# 12V_Distribution_PCB.net
KiCad netlist of a schematic drawn in EasyEDA Pro
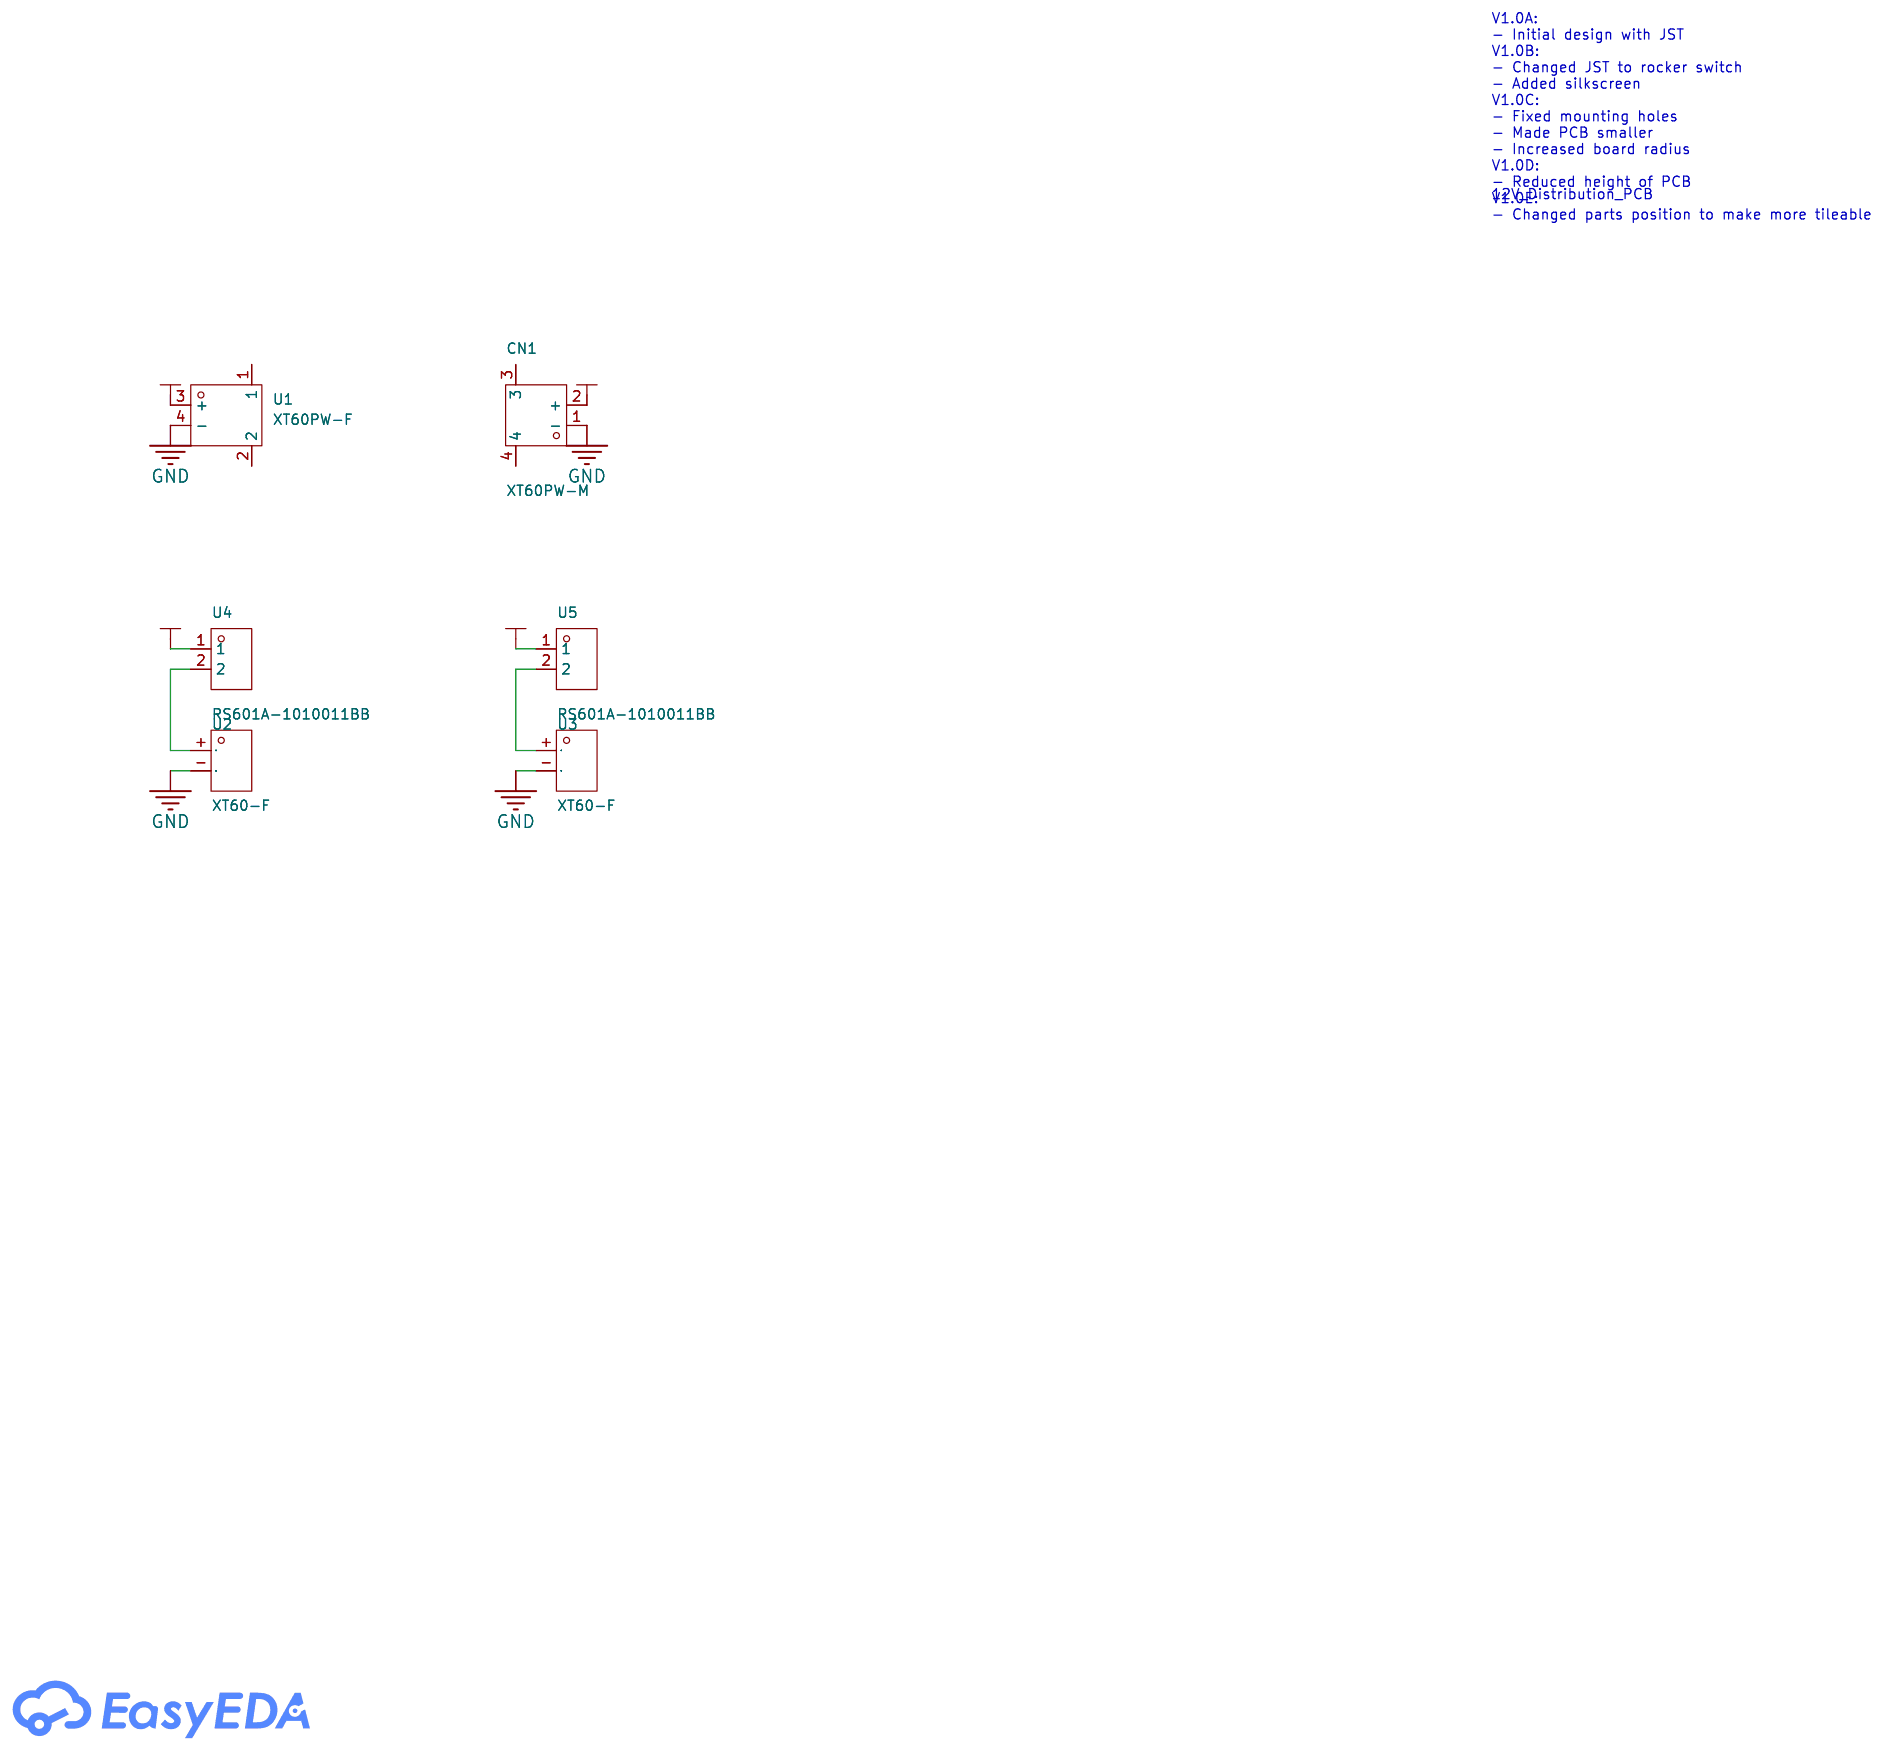
[diagram p0: schematic sheet]

(export (version "E")
  (design (tool "Eeschema 10.0.6"))
  (components
    (comp (ref "CN1")
      (value "XT60PW-M")
      (footprint "easyedapro:CONN-TH_XT60PW-M")
      (fields (field (name "Manufacturer") "AMASS(艾迈斯)"))
      (libsource (lib "easyedapro") (part "XT60PW-M"))
    )
    (comp (ref "U1")
      (value "XT60PW-F")
      (footprint "easyedapro:TH_2P-XT60PW-F")
      (fields (field (name "Manufacturer") "AMASS(艾迈斯)"))
      (libsource (lib "easyedapro") (part "XT60PW-F_C428722"))
    )
    (comp (ref "U2")
      (value "XT60-F")
      (footprint "easyedapro:CONN-TH_XT60PB-F")
      (fields (field (name "Manufacturer") "AMASS(艾迈斯)"))
      (libsource (lib "easyedapro") (part "XT60-F"))
    )
    (comp (ref "U3")
      (value "XT60-F")
      (footprint "easyedapro:CONN-TH_XT60PB-F")
      (fields (field (name "Manufacturer") "AMASS(艾迈斯)"))
      (libsource (lib "easyedapro") (part "XT60-F"))
    )
    (comp (ref "U4")
      (value "RS601A-1010011BB")
      (footprint "easyedapro:SW-TH_RS601A-1010011BB")
      (fields (field (name "Manufacturer") "HCTL(华灿天禄)"))
      (libsource (lib "easyedapro") (part "RS601A-1010011BB_C2885779"))
    )
    (comp (ref "U5")
      (value "RS601A-1010011BB")
      (footprint "easyedapro:SW-TH_RS601A-1010011BB")
      (fields (field (name "Manufacturer") "HCTL(华灿天禄)"))
      (libsource (lib "easyedapro") (part "RS601A-1010011BB_C2885779"))
    )
  )
  (nets
    (net (code "1") (name "+12V") (class "Default")
      (node (ref "CN1") (pin "2") (pinfunction "+_2") (pintype "unspecified"))
      (node (ref "U1") (pin "3") (pinfunction "+_3") (pintype "unspecified"))
      (node (ref "U4") (pin "1") (pinfunction "1_1") (pintype "unspecified"))
      (node (ref "U5") (pin "1") (pinfunction "1_1") (pintype "unspecified"))
    )
    (net (code "2") (name "GND") (class "Default")
      (node (ref "CN1") (pin "1") (pinfunction "-_1") (pintype "unspecified"))
      (node (ref "U1") (pin "4") (pinfunction "-_4") (pintype "unspecified"))
      (node (ref "U2") (pin "-") (pinfunction "2_-") (pintype "input"))
      (node (ref "U3") (pin "-") (pinfunction "2_-") (pintype "input"))
    )
    (net (code "3") (name "Net-(U2-1)") (class "Default")
      (node (ref "U2") (pin "+") (pinfunction "1_+") (pintype "input"))
      (node (ref "U4") (pin "2") (pinfunction "2_2") (pintype "unspecified"))
    )
    (net (code "4") (name "Net-(U3-1)") (class "Default")
      (node (ref "U3") (pin "+") (pinfunction "1_+") (pintype "input"))
      (node (ref "U5") (pin "2") (pinfunction "2_2") (pintype "unspecified"))
    )
    (net (code "5") (name "unconnected-(CN1-Pad3)") (class "Default")
      (node (ref "CN1") (pin "3") (pinfunction "3_3") (pintype "unspecified"))
    )
    (net (code "6") (name "unconnected-(CN1-Pad4)") (class "Default")
      (node (ref "CN1") (pin "4") (pinfunction "4_4") (pintype "unspecified"))
    )
    (net (code "7") (name "unconnected-(U1-Pad1)") (class "Default")
      (node (ref "U1") (pin "1") (pinfunction "1_1") (pintype "unspecified"))
    )
    (net (code "8") (name "unconnected-(U1-Pad2)") (class "Default")
      (node (ref "U1") (pin "2") (pinfunction "2_2") (pintype "unspecified"))
    )
  )
)
